# SOM_POWER.net
KiCad netlist of a schematic drawn in Altium Designer
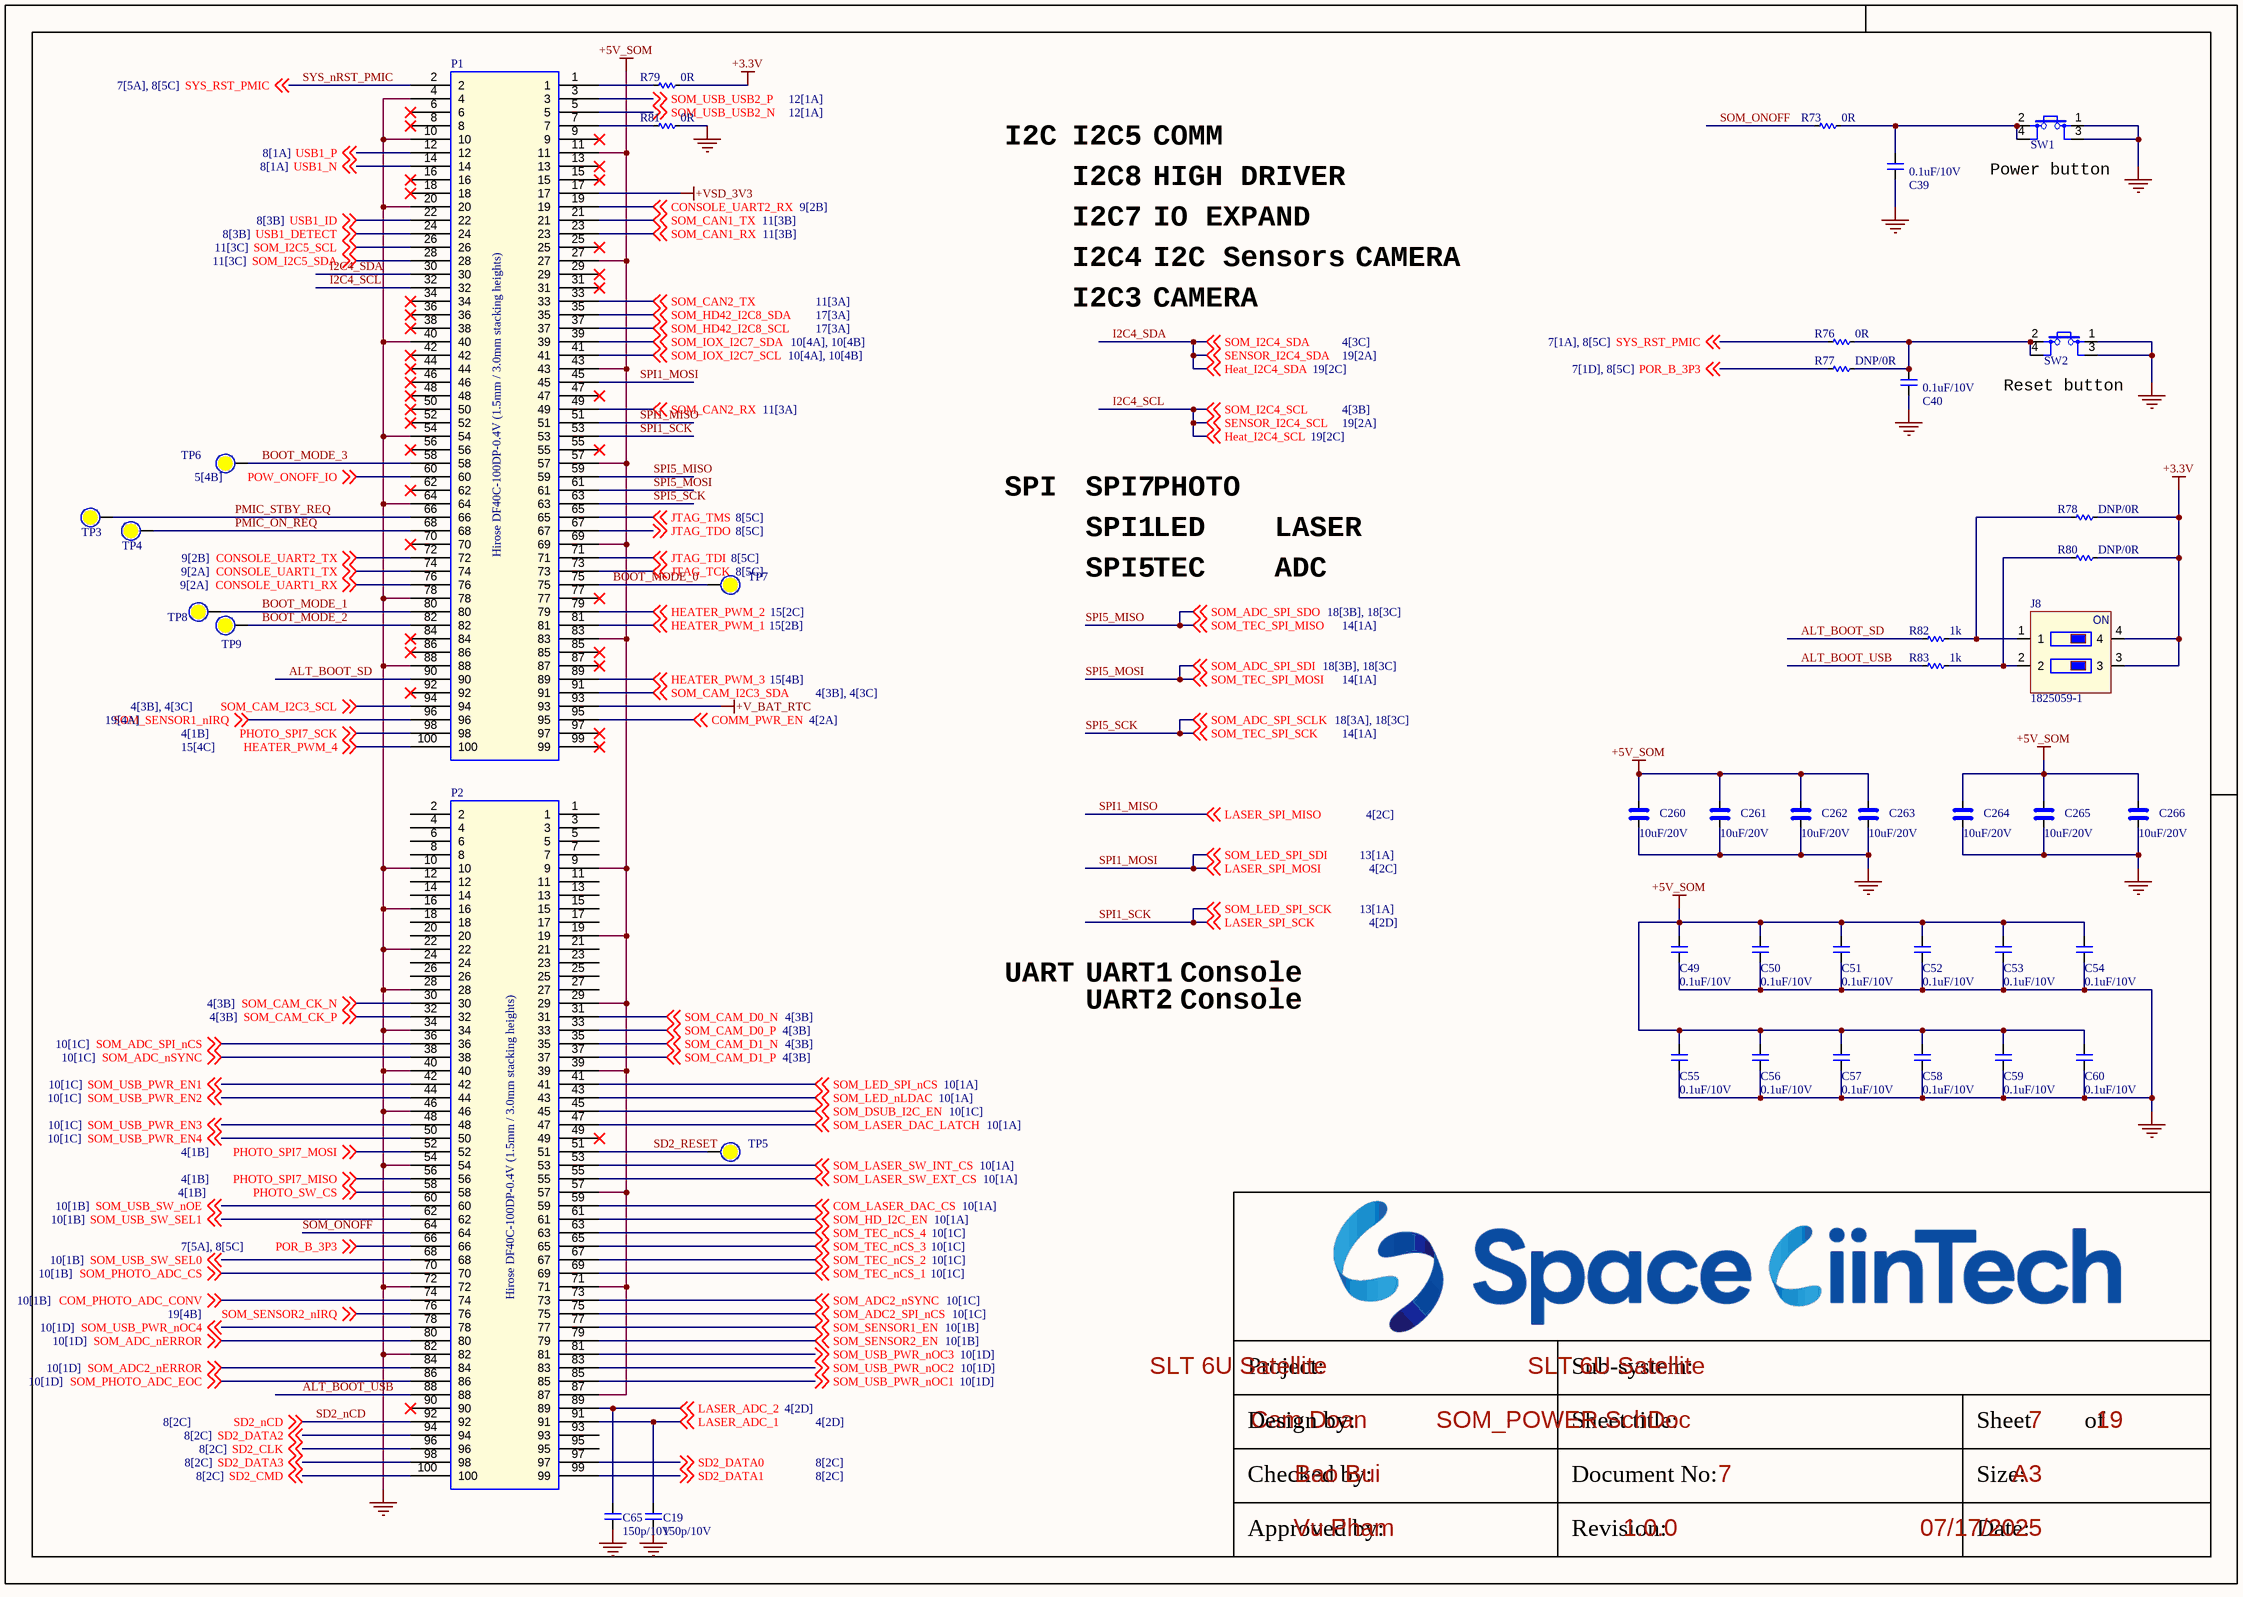
[diagram p0: SOM_POWER.SchDoc]

(export (version "E")
  (design (tool "Eeschema 10.0.6"))
  (components
    (comp (ref "C19")
      (value "150p/10V")
      (footprint "CAP_C_1005X60")
      (description "CAP CHIP")
      (libsource (lib "LABLIB") (part "_CAP_C_2"))
    )
    (comp (ref "C39")
      (value "0.1uF/10V")
      (footprint "CAP_C_1005X60")
      (description "CAP CHIP")
      (libsource (lib "LABLIB") (part "_CAP_C_2"))
    )
    (comp (ref "C40")
      (value "0.1uF/10V")
      (footprint "CAP_C_1005X60")
      (description "CAP CHIP")
      (libsource (lib "LABLIB") (part "_CAP_C_2"))
    )
    (comp (ref "C49")
      (value "0.1uF/10V")
      (footprint "CAP_C_1005X60")
      (description "CAP CHIP")
      (libsource (lib "LABLIB") (part "_CAP_C_2"))
    )
    (comp (ref "C50")
      (value "0.1uF/10V")
      (footprint "CAP_C_1005X60")
      (description "CAP CHIP")
      (libsource (lib "LABLIB") (part "_CAP_C_2"))
    )
    (comp (ref "C51")
      (value "0.1uF/10V")
      (footprint "CAP_C_1005X60")
      (description "CAP CHIP")
      (libsource (lib "LABLIB") (part "_CAP_C_2"))
    )
    (comp (ref "C52")
      (value "0.1uF/10V")
      (footprint "CAP_C_1005X60")
      (description "CAP CHIP")
      (libsource (lib "LABLIB") (part "_CAP_C_2"))
    )
    (comp (ref "C53")
      (value "0.1uF/10V")
      (footprint "CAP_C_1005X60")
      (description "CAP CHIP")
      (libsource (lib "LABLIB") (part "_CAP_C_2"))
    )
    (comp (ref "C54")
      (value "0.1uF/10V")
      (footprint "CAP_C_1005X60")
      (description "CAP CHIP")
      (libsource (lib "LABLIB") (part "_CAP_C_2"))
    )
    (comp (ref "C55")
      (value "0.1uF/10V")
      (footprint "CAP_C_1005X60")
      (description "CAP CHIP")
      (libsource (lib "LABLIB") (part "_CAP_C_2"))
    )
    (comp (ref "C56")
      (value "0.1uF/10V")
      (footprint "CAP_C_1005X60")
      (description "CAP CHIP")
      (libsource (lib "LABLIB") (part "_CAP_C_2"))
    )
    (comp (ref "C57")
      (value "0.1uF/10V")
      (footprint "CAP_C_1005X60")
      (description "CAP CHIP")
      (libsource (lib "LABLIB") (part "_CAP_C_2"))
    )
    (comp (ref "C58")
      (value "0.1uF/10V")
      (footprint "CAP_C_1005X60")
      (description "CAP CHIP")
      (libsource (lib "LABLIB") (part "_CAP_C_2"))
    )
    (comp (ref "C59")
      (value "0.1uF/10V")
      (footprint "CAP_C_1005X60")
      (description "CAP CHIP")
      (libsource (lib "LABLIB") (part "_CAP_C_2"))
    )
    (comp (ref "C60")
      (value "0.1uF/10V")
      (footprint "CAP_C_1005X60")
      (description "CAP CHIP")
      (libsource (lib "LABLIB") (part "_CAP_C_2"))
    )
    (comp (ref "C65")
      (value "150p/10V")
      (footprint "CAP_C_1005X60")
      (description "CAP CHIP")
      (libsource (lib "LABLIB") (part "_CAP_C_2"))
    )
    (comp (ref "C260")
      (value "10uF/20V")
      (footprint "CAP_C_2012X110")
      (description "CAP CHIP High Value")
      (libsource (lib "LABLIB") (part "_CAP_C_High_2"))
    )
    (comp (ref "C261")
      (value "10uF/20V")
      (footprint "CAP_C_2012X110")
      (description "CAP CHIP High Value")
      (libsource (lib "LABLIB") (part "_CAP_C_High_2"))
    )
    (comp (ref "C262")
      (value "10uF/20V")
      (footprint "CAP_C_2012X110")
      (description "CAP CHIP High Value")
      (libsource (lib "LABLIB") (part "_CAP_C_High_2"))
    )
    (comp (ref "C263")
      (value "10uF/20V")
      (footprint "CAP_C_2012X110")
      (description "CAP CHIP High Value")
      (libsource (lib "LABLIB") (part "_CAP_C_High_2"))
    )
    (comp (ref "C264")
      (value "10uF/20V")
      (footprint "CAP_C_2012X110")
      (description "CAP CHIP High Value")
      (libsource (lib "LABLIB") (part "_CAP_C_High_2"))
    )
    (comp (ref "C265")
      (value "10uF/20V")
      (footprint "CAP_C_2012X110")
      (description "CAP CHIP High Value")
      (libsource (lib "LABLIB") (part "_CAP_C_High_2"))
    )
    (comp (ref "C266")
      (value "10uF/20V")
      (footprint "CAP_C_2012X110")
      (description "CAP CHIP High Value")
      (libsource (lib "LABLIB") (part "_CAP_C_High_2"))
    )
    (comp (ref "J8")
      (value "1825059-1")
      (footprint "SW_1825059-1")
      (libsource (lib "LABLIB") (part "DIP_SW_2x2"))
    )
    (comp (ref "P1")
      (value "Hirose DF40C-100DP-0.4V (1.5mm / 3.0mm stacking heights)")
      (footprint "B2B04M2X50R")
      (libsource (lib "*") (part "Hirose DF40C-100DP-0_0.4V"))
    )
    (comp (ref "P2")
      (value "Hirose DF40C-100DP-0.4V (1.5mm / 3.0mm stacking heights)")
      (footprint "B2B04M2X50R")
      (libsource (lib "*") (part "Hirose DF40C-100DP-0_1.4V"))
    )
    (comp (ref "R73")
      (value "0R")
      (footprint "RES_C_1005X40")
      (description "RES")
      (libsource (lib "LABLIB") (part "_RES_B_2"))
    )
    (comp (ref "R76")
      (value "0R")
      (footprint "RES_C_1005X40")
      (description "RES")
      (libsource (lib "LABLIB") (part "_RES_B_2"))
    )
    (comp (ref "R77")
      (value "DNP/0R")
      (footprint "RES_C_1005X40")
      (description "RES")
      (libsource (lib "LABLIB") (part "_RES_B_2"))
    )
    (comp (ref "R78")
      (value "DNP/0R")
      (footprint "RES_C_1005X40")
      (description "RES")
      (libsource (lib "LABLIB") (part "_RES_B_2"))
    )
    (comp (ref "R79")
      (value "0R")
      (footprint "RES_C_1005X40")
      (description "RES")
      (libsource (lib "LABLIB") (part "_RES_B_2"))
    )
    (comp (ref "R80")
      (value "DNP/0R")
      (footprint "RES_C_1005X40")
      (description "RES")
      (libsource (lib "LABLIB") (part "_RES_B_2"))
    )
    (comp (ref "R81")
      (value "0R")
      (footprint "RES_C_1005X40")
      (description "RES")
      (libsource (lib "LABLIB") (part "_RES_B_2"))
    )
    (comp (ref "R82")
      (value "1k")
      (footprint "RES_C_1005X40")
      (description "RES")
      (libsource (lib "LABLIB") (part "_RES_B_2"))
    )
    (comp (ref "R83")
      (value "1k")
      (footprint "RES_C_1005X40")
      (description "RES")
      (libsource (lib "LABLIB") (part "_RES_B_2"))
    )
    (comp (ref "SW1")
      (value "PushB")
      (footprint "TACTSW6x6SM")
      (libsource (lib "*") (part "TACT SW 6x6mm SMT"))
    )
    (comp (ref "SW2")
      (value "PushB")
      (footprint "TACTSW6x6SM")
      (libsource (lib "*") (part "TACT SW 6x6mm SMT"))
    )
    (comp (ref "TP3")
      (value "~")
      (footprint "Testpoint_TH_D130H80")
      (description "Test Point")
      (libsource (lib "") (part "Test Point_1"))
    )
    (comp (ref "TP4")
      (value "~")
      (footprint "Testpoint_TH_D130H80")
      (description "Test Point")
      (libsource (lib "") (part "Test Point_1"))
    )
    (comp (ref "TP5")
      (value "~")
      (footprint "Testpoint_TH_D130H80")
      (description "Test Point")
      (libsource (lib "LABLIB") (part "Test Point"))
    )
    (comp (ref "TP6")
      (value "~")
      (footprint "Testpoint_TH_D130H80")
      (description "Test Point")
      (libsource (lib "") (part "Test Point_2"))
    )
    (comp (ref "TP7")
      (value "~")
      (footprint "Testpoint_TH_D130H80")
      (description "Test Point")
      (libsource (lib "LABLIB") (part "Test Point"))
    )
    (comp (ref "TP8")
      (value "~")
      (footprint "Testpoint_TH_D130H80")
      (description "Test Point")
      (libsource (lib "") (part "Test Point_2"))
    )
    (comp (ref "TP9")
      (value "~")
      (footprint "Testpoint_TH_D130H80")
      (description "Test Point")
      (libsource (lib "") (part "Test Point_2"))
    )
  )
  (nets
    (net (code "1") (name "+3.3V") (class "Default")
      (node (ref "J8") (pin "3") (pinfunction "3_3") (pintype "passive"))
      (node (ref "J8") (pin "4") (pinfunction "4_4") (pintype "passive"))
      (node (ref "R78") (pin "1") (pinfunction "1_1") (pintype "passive"))
      (node (ref "R79") (pin "1") (pinfunction "1_1") (pintype "passive"))
      (node (ref "R80") (pin "1") (pinfunction "1_1") (pintype "passive"))
    )
    (net (code "2") (name "+5V_SOM") (class "Default")
      (node (ref "C260") (pin "1") (pinfunction "1_1") (pintype "passive"))
      (node (ref "C261") (pin "1") (pinfunction "1_1") (pintype "passive"))
      (node (ref "C262") (pin "1") (pinfunction "1_1") (pintype "passive"))
      (node (ref "C263") (pin "1") (pinfunction "1_1") (pintype "passive"))
      (node (ref "C264") (pin "1") (pinfunction "1_1") (pintype "passive"))
      (node (ref "C265") (pin "1") (pinfunction "1_1") (pintype "passive"))
      (node (ref "C266") (pin "1") (pinfunction "1_1") (pintype "passive"))
      (node (ref "C49") (pin "2") (pinfunction "2_2") (pintype "passive"))
      (node (ref "C50") (pin "2") (pinfunction "2_2") (pintype "passive"))
      (node (ref "C51") (pin "2") (pinfunction "2_2") (pintype "passive"))
      (node (ref "C52") (pin "2") (pinfunction "2_2") (pintype "passive"))
      (node (ref "C53") (pin "2") (pinfunction "2_2") (pintype "passive"))
      (node (ref "C54") (pin "2") (pinfunction "2_2") (pintype "passive"))
      (node (ref "C55") (pin "2") (pinfunction "2_2") (pintype "passive"))
      (node (ref "C56") (pin "2") (pinfunction "2_2") (pintype "passive"))
      (node (ref "C57") (pin "2") (pinfunction "2_2") (pintype "passive"))
      (node (ref "C58") (pin "2") (pinfunction "2_2") (pintype "passive"))
      (node (ref "C59") (pin "2") (pinfunction "2_2") (pintype "passive"))
      (node (ref "C60") (pin "2") (pinfunction "2_2") (pintype "passive"))
      (node (ref "P1") (pin "11") (pinfunction "11_11") (pintype "passive"))
      (node (ref "P1") (pin "27") (pinfunction "27_27") (pintype "passive"))
      (node (ref "P1") (pin "43") (pinfunction "43_43") (pintype "passive"))
      (node (ref "P1") (pin "57") (pinfunction "57_57") (pintype "passive"))
      (node (ref "P1") (pin "69") (pinfunction "69_69") (pintype "passive"))
      (node (ref "P1") (pin "83") (pinfunction "83_83") (pintype "passive"))
      (node (ref "P2") (pin "19") (pinfunction "19_19") (pintype "passive"))
      (node (ref "P2") (pin "29") (pinfunction "29_29") (pintype "passive"))
      (node (ref "P2") (pin "39") (pinfunction "39_39") (pintype "passive"))
      (node (ref "P2") (pin "57") (pinfunction "57_57") (pintype "passive"))
      (node (ref "P2") (pin "71") (pinfunction "71_71") (pintype "passive"))
      (node (ref "P2") (pin "87") (pinfunction "87_87") (pintype "passive"))
      (node (ref "P2") (pin "9") (pinfunction "9_9") (pintype "passive"))
    )
    (net (code "3") (name "+VSD_3V3") (class "Default")
      (node (ref "P1") (pin "17") (pinfunction "17_17") (pintype "passive"))
    )
    (net (code "4") (name "+V_BAT_RTC") (class "Default")
      (node (ref "P1") (pin "93") (pinfunction "93_93") (pintype "passive"))
    )
    (net (code "5") (name "/ALT_BOOT_SD") (class "Default")
      (node (ref "P1") (pin "90") (pinfunction "90_90") (pintype "passive"))
      (node (ref "R82") (pin "2") (pinfunction "2_2") (pintype "passive"))
    )
    (net (code "6") (name "/ALT_BOOT_USB") (class "Default")
      (node (ref "P2") (pin "88") (pinfunction "88_88") (pintype "passive"))
      (node (ref "R83") (pin "2") (pinfunction "2_2") (pintype "passive"))
    )
    (net (code "7") (name "/BOOT_MODE_0") (class "Default")
      (node (ref "P1") (pin "75") (pinfunction "75_75") (pintype "passive"))
      (node (ref "TP7") (pin "0") (pinfunction "0_0") (pintype "passive"))
    )
    (net (code "8") (name "/BOOT_MODE_1") (class "Default")
      (node (ref "P1") (pin "80") (pinfunction "80_80") (pintype "passive"))
      (node (ref "TP8") (pin "0") (pinfunction "0_0") (pintype "passive"))
    )
    (net (code "9") (name "/BOOT_MODE_2") (class "Default")
      (node (ref "P1") (pin "82") (pinfunction "82_82") (pintype "passive"))
      (node (ref "TP9") (pin "0") (pinfunction "0_0") (pintype "passive"))
    )
    (net (code "10") (name "/BOOT_MODE_3") (class "Default")
      (node (ref "P1") (pin "58") (pinfunction "58_58") (pintype "passive"))
      (node (ref "TP6") (pin "0") (pinfunction "0_0") (pintype "passive"))
    )
    (net (code "11") (name "/PMIC_ON_REQ") (class "Default")
      (node (ref "P1") (pin "68") (pinfunction "68_68") (pintype "passive"))
      (node (ref "TP4") (pin "0") (pinfunction "0_0") (pintype "passive"))
    )
    (net (code "12") (name "/PMIC_STBY_REQ") (class "Default")
      (node (ref "P1") (pin "66") (pinfunction "66_66") (pintype "passive"))
      (node (ref "TP3") (pin "0") (pinfunction "0_0") (pintype "passive"))
    )
    (net (code "13") (name "/SD2_RESET") (class "Default")
      (node (ref "P2") (pin "51") (pinfunction "51_51") (pintype "passive"))
      (node (ref "TP5") (pin "0") (pinfunction "0_0") (pintype "passive"))
    )
    (net (code "14") (name "/SOM_ONOFF") (class "Default")
      (node (ref "P2") (pin "64") (pinfunction "64_64") (pintype "passive"))
      (node (ref "R73") (pin "2") (pinfunction "2_2") (pintype "passive"))
    )
    (net (code "15") (name "COMM_PWR_EN") (class "Default")
      (node (ref "P1") (pin "95") (pinfunction "95_95") (pintype "passive"))
    )
    (net (code "16") (name "COM_LASER_DAC_CS") (class "Default")
      (node (ref "P2") (pin "59") (pinfunction "59_59") (pintype "passive"))
    )
    (net (code "17") (name "COM_PHOTO_ADC_CONV") (class "Default")
      (node (ref "P2") (pin "74") (pinfunction "74_74") (pintype "passive"))
    )
    (net (code "18") (name "CONSOLE_UART1_RX") (class "Default")
      (node (ref "P1") (pin "76") (pinfunction "76_76") (pintype "passive"))
    )
    (net (code "19") (name "CONSOLE_UART1_TX") (class "Default")
      (node (ref "P1") (pin "74") (pinfunction "74_74") (pintype "passive"))
    )
    (net (code "20") (name "CONSOLE_UART2_RX") (class "Default")
      (node (ref "P1") (pin "19") (pinfunction "19_19") (pintype "passive"))
    )
    (net (code "21") (name "CONSOLE_UART2_TX") (class "Default")
      (node (ref "P1") (pin "72") (pinfunction "72_72") (pintype "passive"))
    )
    (net (code "22") (name "GND") (class "Default")
      (node (ref "C19") (pin "2") (pinfunction "2_2") (pintype "passive"))
      (node (ref "C260") (pin "2") (pinfunction "2_2") (pintype "passive"))
      (node (ref "C261") (pin "2") (pinfunction "2_2") (pintype "passive"))
      (node (ref "C262") (pin "2") (pinfunction "2_2") (pintype "passive"))
      (node (ref "C263") (pin "2") (pinfunction "2_2") (pintype "passive"))
      (node (ref "C264") (pin "2") (pinfunction "2_2") (pintype "passive"))
      (node (ref "C265") (pin "2") (pinfunction "2_2") (pintype "passive"))
      (node (ref "C266") (pin "2") (pinfunction "2_2") (pintype "passive"))
      (node (ref "C39") (pin "1") (pinfunction "1_1") (pintype "passive"))
      (node (ref "C40") (pin "1") (pinfunction "1_1") (pintype "passive"))
      (node (ref "C49") (pin "1") (pinfunction "1_1") (pintype "passive"))
      (node (ref "C50") (pin "1") (pinfunction "1_1") (pintype "passive"))
      (node (ref "C51") (pin "1") (pinfunction "1_1") (pintype "passive"))
      (node (ref "C52") (pin "1") (pinfunction "1_1") (pintype "passive"))
      (node (ref "C53") (pin "1") (pinfunction "1_1") (pintype "passive"))
      (node (ref "C54") (pin "1") (pinfunction "1_1") (pintype "passive"))
      (node (ref "C55") (pin "1") (pinfunction "1_1") (pintype "passive"))
      (node (ref "C56") (pin "1") (pinfunction "1_1") (pintype "passive"))
      (node (ref "C57") (pin "1") (pinfunction "1_1") (pintype "passive"))
      (node (ref "C58") (pin "1") (pinfunction "1_1") (pintype "passive"))
      (node (ref "C59") (pin "1") (pinfunction "1_1") (pintype "passive"))
      (node (ref "C60") (pin "1") (pinfunction "1_1") (pintype "passive"))
      (node (ref "C65") (pin "2") (pinfunction "2_2") (pintype "passive"))
      (node (ref "P1") (pin "10") (pinfunction "10_10") (pintype "passive"))
      (node (ref "P1") (pin "20") (pinfunction "20_20") (pintype "passive"))
      (node (ref "P1") (pin "4") (pinfunction "4_4") (pintype "passive"))
      (node (ref "P1") (pin "40") (pinfunction "40_40") (pintype "passive"))
      (node (ref "P1") (pin "54") (pinfunction "54_54") (pintype "passive"))
      (node (ref "P1") (pin "64") (pinfunction "64_64") (pintype "passive"))
      (node (ref "P1") (pin "78") (pinfunction "78_78") (pintype "passive"))
      (node (ref "P1") (pin "88") (pinfunction "88_88") (pintype "passive"))
      (node (ref "P2") (pin "10") (pinfunction "10_10") (pintype "passive"))
      (node (ref "P2") (pin "16") (pinfunction "16_16") (pintype "passive"))
      (node (ref "P2") (pin "22") (pinfunction "22_22") (pintype "passive"))
      (node (ref "P2") (pin "28") (pinfunction "28_28") (pintype "passive"))
      (node (ref "P2") (pin "34") (pinfunction "34_34") (pintype "passive"))
      (node (ref "P2") (pin "40") (pinfunction "40_40") (pintype "passive"))
      (node (ref "P2") (pin "46") (pinfunction "46_46") (pintype "passive"))
      (node (ref "P2") (pin "54") (pinfunction "54_54") (pintype "passive"))
      (node (ref "P2") (pin "72") (pinfunction "72_72") (pintype "passive"))
      (node (ref "P2") (pin "82") (pinfunction "82_82") (pintype "passive"))
      (node (ref "R81") (pin "1") (pinfunction "1_1") (pintype "passive"))
      (node (ref "SW1") (pin "1") (pinfunction "1_1") (pintype "passive"))
      (node (ref "SW1") (pin "3") (pinfunction "3_3") (pintype "passive"))
      (node (ref "SW2") (pin "1") (pinfunction "1_1") (pintype "passive"))
      (node (ref "SW2") (pin "3") (pinfunction "3_3") (pintype "passive"))
    )
    (net (code "23") (name "HEATER_PWM_1") (class "Default")
      (node (ref "P1") (pin "81") (pinfunction "81_81") (pintype "passive"))
    )
    (net (code "24") (name "HEATER_PWM_2") (class "Default")
      (node (ref "P1") (pin "79") (pinfunction "79_79") (pintype "passive"))
    )
    (net (code "25") (name "HEATER_PWM_3") (class "Default")
      (node (ref "P1") (pin "89") (pinfunction "89_89") (pintype "passive"))
    )
    (net (code "26") (name "HEATER_PWM_4") (class "Default")
      (node (ref "P1") (pin "100") (pinfunction "100_100") (pintype "passive"))
    )
    (net (code "27") (name "Heat_I2C4_SCL") (class "Default")
      (node (ref "P1") (pin "32") (pinfunction "32_32") (pintype "passive"))
    )
    (net (code "28") (name "Heat_I2C4_SDA") (class "Default")
      (node (ref "P1") (pin "30") (pinfunction "30_30") (pintype "passive"))
    )
    (net (code "29") (name "JTAG_TCK") (class "Default")
      (node (ref "P1") (pin "73") (pinfunction "73_73") (pintype "passive"))
    )
    (net (code "30") (name "JTAG_TDI") (class "Default")
      (node (ref "P1") (pin "71") (pinfunction "71_71") (pintype "passive"))
    )
    (net (code "31") (name "JTAG_TDO") (class "Default")
      (node (ref "P1") (pin "67") (pinfunction "67_67") (pintype "passive"))
    )
    (net (code "32") (name "JTAG_TMS") (class "Default")
      (node (ref "P1") (pin "65") (pinfunction "65_65") (pintype "passive"))
    )
    (net (code "33") (name "LASER_ADC_1") (class "Default")
      (node (ref "C19") (pin "1") (pinfunction "1_1") (pintype "passive"))
      (node (ref "P2") (pin "91") (pinfunction "91_91") (pintype "passive"))
    )
    (net (code "34") (name "LASER_ADC_2") (class "Default")
      (node (ref "C65") (pin "1") (pinfunction "1_1") (pintype "passive"))
      (node (ref "P2") (pin "89") (pinfunction "89_89") (pintype "passive"))
    )
    (net (code "35") (name "LASER_SPI_MISO") (class "Default")
      (node (ref "P1") (pin "51") (pinfunction "51_51") (pintype "passive"))
    )
    (net (code "36") (name "LASER_SPI_MOSI") (class "Default")
      (node (ref "P1") (pin "45") (pinfunction "45_45") (pintype "passive"))
    )
    (net (code "37") (name "LASER_SPI_SCK") (class "Default")
      (node (ref "P1") (pin "53") (pinfunction "53_53") (pintype "passive"))
    )
    (net (code "38") (name "Net-(C39-Pad2)") (class "Default")
      (node (ref "C39") (pin "2") (pinfunction "2_2") (pintype "passive"))
      (node (ref "R73") (pin "1") (pinfunction "1_1") (pintype "passive"))
      (node (ref "SW1") (pin "2") (pinfunction "2_2") (pintype "passive"))
      (node (ref "SW1") (pin "4") (pinfunction "4_4") (pintype "passive"))
    )
    (net (code "39") (name "Net-(C40-Pad2)") (class "Default")
      (node (ref "C40") (pin "2") (pinfunction "2_2") (pintype "passive"))
      (node (ref "R76") (pin "1") (pinfunction "1_1") (pintype "passive"))
      (node (ref "R77") (pin "1") (pinfunction "1_1") (pintype "passive"))
      (node (ref "SW2") (pin "2") (pinfunction "2_2") (pintype "passive"))
      (node (ref "SW2") (pin "4") (pinfunction "4_4") (pintype "passive"))
    )
    (net (code "40") (name "Net-(J8-Pad1)") (class "Default")
      (node (ref "J8") (pin "1") (pinfunction "1_1") (pintype "passive"))
      (node (ref "R78") (pin "2") (pinfunction "2_2") (pintype "passive"))
      (node (ref "R82") (pin "1") (pinfunction "1_1") (pintype "passive"))
    )
    (net (code "41") (name "Net-(J8-Pad2)") (class "Default")
      (node (ref "J8") (pin "2") (pinfunction "2_2") (pintype "passive"))
      (node (ref "R80") (pin "2") (pinfunction "2_2") (pintype "passive"))
      (node (ref "R83") (pin "1") (pinfunction "1_1") (pintype "passive"))
    )
    (net (code "42") (name "Net-(P1-Pad1)") (class "Default")
      (node (ref "P1") (pin "1") (pinfunction "1_1") (pintype "passive"))
      (node (ref "R79") (pin "2") (pinfunction "2_2") (pintype "passive"))
    )
    (net (code "43") (name "Net-(P1-Pad7)") (class "Default")
      (node (ref "P1") (pin "7") (pinfunction "7_7") (pintype "passive"))
      (node (ref "R81") (pin "2") (pinfunction "2_2") (pintype "passive"))
    )
    (net (code "44") (name "PHOTO_SPI7_MISO") (class "Default")
      (node (ref "P2") (pin "56") (pinfunction "56_56") (pintype "passive"))
    )
    (net (code "45") (name "PHOTO_SPI7_MOSI") (class "Default")
      (node (ref "P2") (pin "52") (pinfunction "52_52") (pintype "passive"))
    )
    (net (code "46") (name "PHOTO_SPI7_SCK") (class "Default")
      (node (ref "P1") (pin "98") (pinfunction "98_98") (pintype "passive"))
    )
    (net (code "47") (name "PHOTO_SW_CS") (class "Default")
      (node (ref "P2") (pin "58") (pinfunction "58_58") (pintype "passive"))
    )
    (net (code "48") (name "POR_B_3P3") (class "Default")
      (node (ref "P2") (pin "66") (pinfunction "66_66") (pintype "passive"))
      (node (ref "R77") (pin "2") (pinfunction "2_2") (pintype "passive"))
    )
    (net (code "49") (name "POW_ONOFF_IO") (class "Default")
      (node (ref "P1") (pin "60") (pinfunction "60_60") (pintype "passive"))
    )
    (net (code "50") (name "SD2_CLK") (class "Default")
      (node (ref "P2") (pin "96") (pinfunction "96_96") (pintype "passive"))
    )
    (net (code "51") (name "SD2_CMD") (class "Default")
      (node (ref "P2") (pin "100") (pinfunction "100_100") (pintype "passive"))
    )
    (net (code "52") (name "SD2_DATA0") (class "Default")
      (node (ref "P2") (pin "97") (pinfunction "97_97") (pintype "passive"))
    )
    (net (code "53") (name "SD2_DATA1") (class "Default")
      (node (ref "P2") (pin "99") (pinfunction "99_99") (pintype "passive"))
    )
    (net (code "54") (name "SD2_DATA2") (class "Default")
      (node (ref "P2") (pin "94") (pinfunction "94_94") (pintype "passive"))
    )
    (net (code "55") (name "SD2_DATA3") (class "Default")
      (node (ref "P2") (pin "98") (pinfunction "98_98") (pintype "passive"))
    )
    (net (code "56") (name "SD2_nCD") (class "Default")
      (node (ref "P2") (pin "92") (pinfunction "92_92") (pintype "passive"))
    )
    (net (code "57") (name "SOM_ADC2_SPI_nCS") (class "Default")
      (node (ref "P2") (pin "75") (pinfunction "75_75") (pintype "passive"))
    )
    (net (code "58") (name "SOM_ADC2_nERROR") (class "Default")
      (node (ref "P2") (pin "84") (pinfunction "84_84") (pintype "passive"))
    )
    (net (code "59") (name "SOM_ADC2_nSYNC") (class "Default")
      (node (ref "P2") (pin "73") (pinfunction "73_73") (pintype "passive"))
    )
    (net (code "60") (name "SOM_ADC_SPI_SCLK") (class "Default")
      (node (ref "P1") (pin "63") (pinfunction "63_63") (pintype "passive"))
    )
    (net (code "61") (name "SOM_ADC_SPI_SDI") (class "Default")
      (node (ref "P1") (pin "61") (pinfunction "61_61") (pintype "passive"))
    )
    (net (code "62") (name "SOM_ADC_SPI_SDO") (class "Default")
      (node (ref "P1") (pin "59") (pinfunction "59_59") (pintype "passive"))
    )
    (net (code "63") (name "SOM_ADC_SPI_nCS") (class "Default")
      (node (ref "P2") (pin "36") (pinfunction "36_36") (pintype "passive"))
    )
    (net (code "64") (name "SOM_ADC_nERROR") (class "Default")
      (node (ref "P2") (pin "80") (pinfunction "80_80") (pintype "passive"))
    )
    (net (code "65") (name "SOM_ADC_nSYNC") (class "Default")
      (node (ref "P2") (pin "38") (pinfunction "38_38") (pintype "passive"))
    )
    (net (code "66") (name "SOM_CAM_CK_N") (class "Default")
      (node (ref "P2") (pin "30") (pinfunction "30_30") (pintype "passive"))
    )
    (net (code "67") (name "SOM_CAM_CK_P") (class "Default")
      (node (ref "P2") (pin "32") (pinfunction "32_32") (pintype "passive"))
    )
    (net (code "68") (name "SOM_CAM_D0_N") (class "Default")
      (node (ref "P2") (pin "31") (pinfunction "31_31") (pintype "passive"))
    )
    (net (code "69") (name "SOM_CAM_D0_P") (class "Default")
      (node (ref "P2") (pin "33") (pinfunction "33_33") (pintype "passive"))
    )
    (net (code "70") (name "SOM_CAM_D1_N") (class "Default")
      (node (ref "P2") (pin "35") (pinfunction "35_35") (pintype "passive"))
    )
    (net (code "71") (name "SOM_CAM_D1_P") (class "Default")
      (node (ref "P2") (pin "37") (pinfunction "37_37") (pintype "passive"))
    )
    (net (code "72") (name "SOM_CAM_I2C3_SCL") (class "Default")
      (node (ref "P1") (pin "94") (pinfunction "94_94") (pintype "passive"))
    )
    (net (code "73") (name "SOM_CAM_I2C3_SDA") (class "Default")
      (node (ref "P1") (pin "91") (pinfunction "91_91") (pintype "passive"))
    )
    (net (code "74") (name "SOM_CAN1_RX") (class "Default")
      (node (ref "P1") (pin "23") (pinfunction "23_23") (pintype "passive"))
    )
    (net (code "75") (name "SOM_CAN1_TX") (class "Default")
      (node (ref "P1") (pin "21") (pinfunction "21_21") (pintype "passive"))
    )
    (net (code "76") (name "SOM_CAN2_RX") (class "Default")
      (node (ref "P1") (pin "49") (pinfunction "49_49") (pintype "passive"))
    )
    (net (code "77") (name "SOM_CAN2_TX") (class "Default")
      (node (ref "P1") (pin "33") (pinfunction "33_33") (pintype "passive"))
    )
    (net (code "78") (name "SOM_DSUB_I2C_EN") (class "Default")
      (node (ref "P2") (pin "45") (pinfunction "45_45") (pintype "passive"))
    )
    (net (code "79") (name "SOM_HD42_I2C8_SCL") (class "Default")
      (node (ref "P1") (pin "37") (pinfunction "37_37") (pintype "passive"))
    )
    (net (code "80") (name "SOM_HD42_I2C8_SDA") (class "Default")
      (node (ref "P1") (pin "35") (pinfunction "35_35") (pintype "passive"))
    )
    (net (code "81") (name "SOM_HD_I2C_EN") (class "Default")
      (node (ref "P2") (pin "61") (pinfunction "61_61") (pintype "passive"))
    )
    (net (code "82") (name "SOM_I2C5_SCL") (class "Default")
      (node (ref "P1") (pin "26") (pinfunction "26_26") (pintype "passive"))
    )
    (net (code "83") (name "SOM_I2C5_SDA") (class "Default")
      (node (ref "P1") (pin "28") (pinfunction "28_28") (pintype "passive"))
    )
    (net (code "84") (name "SOM_IOX_I2C7_SCL") (class "Default")
      (node (ref "P1") (pin "41") (pinfunction "41_41") (pintype "passive"))
    )
    (net (code "85") (name "SOM_IOX_I2C7_SDA") (class "Default")
      (node (ref "P1") (pin "39") (pinfunction "39_39") (pintype "passive"))
    )
    (net (code "86") (name "SOM_LASER_DAC_LATCH") (class "Default")
      (node (ref "P2") (pin "47") (pinfunction "47_47") (pintype "passive"))
    )
    (net (code "87") (name "SOM_LASER_SW_EXT_CS") (class "Default")
      (node (ref "P2") (pin "55") (pinfunction "55_55") (pintype "passive"))
    )
    (net (code "88") (name "SOM_LASER_SW_INT_CS") (class "Default")
      (node (ref "P2") (pin "53") (pinfunction "53_53") (pintype "passive"))
    )
    (net (code "89") (name "SOM_LED_SPI_nCS") (class "Default")
      (node (ref "P2") (pin "41") (pinfunction "41_41") (pintype "passive"))
    )
    (net (code "90") (name "SOM_LED_nLDAC") (class "Default")
      (node (ref "P2") (pin "43") (pinfunction "43_43") (pintype "passive"))
    )
    (net (code "91") (name "SOM_PHOTO_ADC_CS") (class "Default")
      (node (ref "P2") (pin "70") (pinfunction "70_70") (pintype "passive"))
    )
    (net (code "92") (name "SOM_PHOTO_ADC_EOC") (class "Default")
      (node (ref "P2") (pin "86") (pinfunction "86_86") (pintype "passive"))
    )
    (net (code "93") (name "SOM_SENSOR1_EN") (class "Default")
      (node (ref "P2") (pin "77") (pinfunction "77_77") (pintype "passive"))
    )
    (net (code "94") (name "SOM_SENSOR1_nIRQ") (class "Default")
      (node (ref "P1") (pin "96") (pinfunction "96_96") (pintype "passive"))
    )
    (net (code "95") (name "SOM_SENSOR2_EN") (class "Default")
      (node (ref "P2") (pin "79") (pinfunction "79_79") (pintype "passive"))
    )
    (net (code "96") (name "SOM_SENSOR2_nIRQ") (class "Default")
      (node (ref "P2") (pin "76") (pinfunction "76_76") (pintype "passive"))
    )
    (net (code "97") (name "SOM_TEC_nCS_1") (class "Default")
      (node (ref "P2") (pin "69") (pinfunction "69_69") (pintype "passive"))
    )
    (net (code "98") (name "SOM_TEC_nCS_2") (class "Default")
      (node (ref "P2") (pin "67") (pinfunction "67_67") (pintype "passive"))
    )
    (net (code "99") (name "SOM_TEC_nCS_3") (class "Default")
      (node (ref "P2") (pin "65") (pinfunction "65_65") (pintype "passive"))
    )
    (net (code "100") (name "SOM_TEC_nCS_4") (class "Default")
      (node (ref "P2") (pin "63") (pinfunction "63_63") (pintype "passive"))
    )
    (net (code "101") (name "SOM_USB_PWR_EN1") (class "Default")
      (node (ref "P2") (pin "42") (pinfunction "42_42") (pintype "passive"))
    )
    (net (code "102") (name "SOM_USB_PWR_EN2") (class "Default")
      (node (ref "P2") (pin "44") (pinfunction "44_44") (pintype "passive"))
    )
    (net (code "103") (name "SOM_USB_PWR_EN3") (class "Default")
      (node (ref "P2") (pin "48") (pinfunction "48_48") (pintype "passive"))
    )
    (net (code "104") (name "SOM_USB_PWR_EN4") (class "Default")
      (node (ref "P2") (pin "50") (pinfunction "50_50") (pintype "passive"))
    )
    (net (code "105") (name "SOM_USB_PWR_nOC1") (class "Default")
      (node (ref "P2") (pin "85") (pinfunction "85_85") (pintype "passive"))
    )
    (net (code "106") (name "SOM_USB_PWR_nOC2") (class "Default")
      (node (ref "P2") (pin "83") (pinfunction "83_83") (pintype "passive"))
    )
    (net (code "107") (name "SOM_USB_PWR_nOC3") (class "Default")
      (node (ref "P2") (pin "81") (pinfunction "81_81") (pintype "passive"))
    )
    (net (code "108") (name "SOM_USB_PWR_nOC4") (class "Default")
      (node (ref "P2") (pin "78") (pinfunction "78_78") (pintype "passive"))
    )
    (net (code "109") (name "SOM_USB_SW_SEL0") (class "Default")
      (node (ref "P2") (pin "68") (pinfunction "68_68") (pintype "passive"))
    )
    (net (code "110") (name "SOM_USB_SW_SEL1") (class "Default")
      (node (ref "P2") (pin "62") (pinfunction "62_62") (pintype "passive"))
    )
    (net (code "111") (name "SOM_USB_SW_nOE") (class "Default")
      (node (ref "P2") (pin "60") (pinfunction "60_60") (pintype "passive"))
    )
    (net (code "112") (name "SOM_USB_USB2_N") (class "Default")
      (node (ref "P1") (pin "5") (pinfunction "5_5") (pintype "passive"))
    )
    (net (code "113") (name "SOM_USB_USB2_P") (class "Default")
      (node (ref "P1") (pin "3") (pinfunction "3_3") (pintype "passive"))
    )
    (net (code "114") (name "SYS_RST_PMIC") (class "Default")
      (node (ref "P1") (pin "2") (pinfunction "2_2") (pintype "passive"))
      (node (ref "R76") (pin "2") (pinfunction "2_2") (pintype "passive"))
    )
    (net (code "115") (name "USB1_DETECT") (class "Default")
      (node (ref "P1") (pin "24") (pinfunction "24_24") (pintype "passive"))
    )
    (net (code "116") (name "USB1_ID") (class "Default")
      (node (ref "P1") (pin "22") (pinfunction "22_22") (pintype "passive"))
    )
    (net (code "117") (name "USB1_N") (class "Default")
      (node (ref "P1") (pin "14") (pinfunction "14_14") (pintype "passive"))
    )
    (net (code "118") (name "USB1_P") (class "Default")
      (node (ref "P1") (pin "12") (pinfunction "12_12") (pintype "passive"))
    )
    (net (code "119") (name "unconnected-(P1-Pad6)") (class "Default")
      (node (ref "P1") (pin "6") (pinfunction "6_6") (pintype "passive+no_connect"))
    )
    (net (code "120") (name "unconnected-(P1-Pad8)") (class "Default")
      (node (ref "P1") (pin "8") (pinfunction "8_8") (pintype "passive+no_connect"))
    )
    (net (code "121") (name "unconnected-(P1-Pad9)") (class "Default")
      (node (ref "P1") (pin "9") (pinfunction "9_9") (pintype "passive+no_connect"))
    )
    (net (code "122") (name "unconnected-(P1-Pad13)") (class "Default")
      (node (ref "P1") (pin "13") (pinfunction "13_13") (pintype "passive+no_connect"))
    )
    (net (code "123") (name "unconnected-(P1-Pad15)") (class "Default")
      (node (ref "P1") (pin "15") (pinfunction "15_15") (pintype "passive+no_connect"))
    )
    (net (code "124") (name "unconnected-(P1-Pad16)") (class "Default")
      (node (ref "P1") (pin "16") (pinfunction "16_16") (pintype "passive+no_connect"))
    )
    (net (code "125") (name "unconnected-(P1-Pad18)") (class "Default")
      (node (ref "P1") (pin "18") (pinfunction "18_18") (pintype "passive+no_connect"))
    )
    (net (code "126") (name "unconnected-(P1-Pad25)") (class "Default")
      (node (ref "P1") (pin "25") (pinfunction "25_25") (pintype "passive+no_connect"))
    )
    (net (code "127") (name "unconnected-(P1-Pad29)") (class "Default")
      (node (ref "P1") (pin "29") (pinfunction "29_29") (pintype "passive+no_connect"))
    )
    (net (code "128") (name "unconnected-(P1-Pad31)") (class "Default")
      (node (ref "P1") (pin "31") (pinfunction "31_31") (pintype "passive+no_connect"))
    )
    (net (code "129") (name "unconnected-(P1-Pad34)") (class "Default")
      (node (ref "P1") (pin "34") (pinfunction "34_34") (pintype "passive+no_connect"))
    )
    (net (code "130") (name "unconnected-(P1-Pad36)") (class "Default")
      (node (ref "P1") (pin "36") (pinfunction "36_36") (pintype "passive+no_connect"))
    )
    (net (code "131") (name "unconnected-(P1-Pad38)") (class "Default")
      (node (ref "P1") (pin "38") (pinfunction "38_38") (pintype "passive+no_connect"))
    )
    (net (code "132") (name "unconnected-(P1-Pad42)") (class "Default")
      (node (ref "P1") (pin "42") (pinfunction "42_42") (pintype "passive+no_connect"))
    )
    (net (code "133") (name "unconnected-(P1-Pad44)") (class "Default")
      (node (ref "P1") (pin "44") (pinfunction "44_44") (pintype "passive+no_connect"))
    )
    (net (code "134") (name "unconnected-(P1-Pad46)") (class "Default")
      (node (ref "P1") (pin "46") (pinfunction "46_46") (pintype "passive+no_connect"))
    )
    (net (code "135") (name "unconnected-(P1-Pad47)") (class "Default")
      (node (ref "P1") (pin "47") (pinfunction "47_47") (pintype "passive+no_connect"))
    )
    (net (code "136") (name "unconnected-(P1-Pad48)") (class "Default")
      (node (ref "P1") (pin "48") (pinfunction "48_48") (pintype "passive+no_connect"))
    )
    (net (code "137") (name "unconnected-(P1-Pad50)") (class "Default")
      (node (ref "P1") (pin "50") (pinfunction "50_50") (pintype "passive+no_connect"))
    )
    (net (code "138") (name "unconnected-(P1-Pad52)") (class "Default")
      (node (ref "P1") (pin "52") (pinfunction "52_52") (pintype "passive+no_connect"))
    )
    (net (code "139") (name "unconnected-(P1-Pad55)") (class "Default")
      (node (ref "P1") (pin "55") (pinfunction "55_55") (pintype "passive+no_connect"))
    )
    (net (code "140") (name "unconnected-(P1-Pad56)") (class "Default")
      (node (ref "P1") (pin "56") (pinfunction "56_56") (pintype "passive+no_connect"))
    )
    (net (code "141") (name "unconnected-(P1-Pad62)") (class "Default")
      (node (ref "P1") (pin "62") (pinfunction "62_62") (pintype "passive+no_connect"))
    )
    (net (code "142") (name "unconnected-(P1-Pad70)") (class "Default")
      (node (ref "P1") (pin "70") (pinfunction "70_70") (pintype "passive+no_connect"))
    )
    (net (code "143") (name "unconnected-(P1-Pad77)") (class "Default")
      (node (ref "P1") (pin "77") (pinfunction "77_77") (pintype "passive+no_connect"))
    )
    (net (code "144") (name "unconnected-(P1-Pad84)") (class "Default")
      (node (ref "P1") (pin "84") (pinfunction "84_84") (pintype "passive+no_connect"))
    )
    (net (code "145") (name "unconnected-(P1-Pad85)") (class "Default")
      (node (ref "P1") (pin "85") (pinfunction "85_85") (pintype "passive+no_connect"))
    )
    (net (code "146") (name "unconnected-(P1-Pad86)") (class "Default")
      (node (ref "P1") (pin "86") (pinfunction "86_86") (pintype "passive+no_connect"))
    )
    (net (code "147") (name "unconnected-(P1-Pad87)") (class "Default")
      (node (ref "P1") (pin "87") (pinfunction "87_87") (pintype "passive+no_connect"))
    )
    (net (code "148") (name "unconnected-(P1-Pad92)") (class "Default")
      (node (ref "P1") (pin "92") (pinfunction "92_92") (pintype "passive+no_connect"))
    )
    (net (code "149") (name "unconnected-(P1-Pad97)") (class "Default")
      (node (ref "P1") (pin "97") (pinfunction "97_97") (pintype "passive+no_connect"))
    )
    (net (code "150") (name "unconnected-(P1-Pad99)") (class "Default")
      (node (ref "P1") (pin "99") (pinfunction "99_99") (pintype "passive+no_connect"))
    )
    (net (code "151") (name "unconnected-(P2-Pad1)") (class "Default")
      (node (ref "P2") (pin "1") (pinfunction "1_1") (pintype "passive"))
    )
    (net (code "152") (name "unconnected-(P2-Pad2)") (class "Default")
      (node (ref "P2") (pin "2") (pinfunction "2_2") (pintype "passive"))
    )
    (net (code "153") (name "unconnected-(P2-Pad3)") (class "Default")
      (node (ref "P2") (pin "3") (pinfunction "3_3") (pintype "passive"))
    )
    (net (code "154") (name "unconnected-(P2-Pad4)") (class "Default")
      (node (ref "P2") (pin "4") (pinfunction "4_4") (pintype "passive"))
    )
    (net (code "155") (name "unconnected-(P2-Pad5)") (class "Default")
      (node (ref "P2") (pin "5") (pinfunction "5_5") (pintype "passive"))
    )
    (net (code "156") (name "unconnected-(P2-Pad6)") (class "Default")
      (node (ref "P2") (pin "6") (pinfunction "6_6") (pintype "passive"))
    )
    (net (code "157") (name "unconnected-(P2-Pad7)") (class "Default")
      (node (ref "P2") (pin "7") (pinfunction "7_7") (pintype "passive"))
    )
    (net (code "158") (name "unconnected-(P2-Pad8)") (class "Default")
      (node (ref "P2") (pin "8") (pinfunction "8_8") (pintype "passive"))
    )
    (net (code "159") (name "unconnected-(P2-Pad11)") (class "Default")
      (node (ref "P2") (pin "11") (pinfunction "11_11") (pintype "passive"))
    )
    (net (code "160") (name "unconnected-(P2-Pad12)") (class "Default")
      (node (ref "P2") (pin "12") (pinfunction "12_12") (pintype "passive"))
    )
    (net (code "161") (name "unconnected-(P2-Pad13)") (class "Default")
      (node (ref "P2") (pin "13") (pinfunction "13_13") (pintype "passive"))
    )
    (net (code "162") (name "unconnected-(P2-Pad14)") (class "Default")
      (node (ref "P2") (pin "14") (pinfunction "14_14") (pintype "passive"))
    )
    (net (code "163") (name "unconnected-(P2-Pad15)") (class "Default")
      (node (ref "P2") (pin "15") (pinfunction "15_15") (pintype "passive"))
    )
    (net (code "164") (name "unconnected-(P2-Pad17)") (class "Default")
      (node (ref "P2") (pin "17") (pinfunction "17_17") (pintype "passive"))
    )
    (net (code "165") (name "unconnected-(P2-Pad18)") (class "Default")
      (node (ref "P2") (pin "18") (pinfunction "18_18") (pintype "passive"))
    )
    (net (code "166") (name "unconnected-(P2-Pad20)") (class "Default")
      (node (ref "P2") (pin "20") (pinfunction "20_20") (pintype "passive"))
    )
    (net (code "167") (name "unconnected-(P2-Pad21)") (class "Default")
      (node (ref "P2") (pin "21") (pinfunction "21_21") (pintype "passive"))
    )
    (net (code "168") (name "unconnected-(P2-Pad23)") (class "Default")
      (node (ref "P2") (pin "23") (pinfunction "23_23") (pintype "passive"))
    )
    (net (code "169") (name "unconnected-(P2-Pad24)") (class "Default")
      (node (ref "P2") (pin "24") (pinfunction "24_24") (pintype "passive"))
    )
    (net (code "170") (name "unconnected-(P2-Pad25)") (class "Default")
      (node (ref "P2") (pin "25") (pinfunction "25_25") (pintype "passive"))
    )
    (net (code "171") (name "unconnected-(P2-Pad26)") (class "Default")
      (node (ref "P2") (pin "26") (pinfunction "26_26") (pintype "passive"))
    )
    (net (code "172") (name "unconnected-(P2-Pad27)") (class "Default")
      (node (ref "P2") (pin "27") (pinfunction "27_27") (pintype "passive"))
    )
    (net (code "173") (name "unconnected-(P2-Pad49)") (class "Default")
      (node (ref "P2") (pin "49") (pinfunction "49_49") (pintype "passive+no_connect"))
    )
    (net (code "174") (name "unconnected-(P2-Pad90)") (class "Default")
      (node (ref "P2") (pin "90") (pinfunction "90_90") (pintype "passive+no_connect"))
    )
    (net (code "175") (name "unconnected-(P2-Pad93)") (class "Default")
      (node (ref "P2") (pin "93") (pinfunction "93_93") (pintype "passive"))
    )
    (net (code "176") (name "unconnected-(P2-Pad95)") (class "Default")
      (node (ref "P2") (pin "95") (pinfunction "95_95") (pintype "passive"))
    )
  )
)
